# Sheet1.net
KiCad netlist of a schematic drawn in Altium Designer
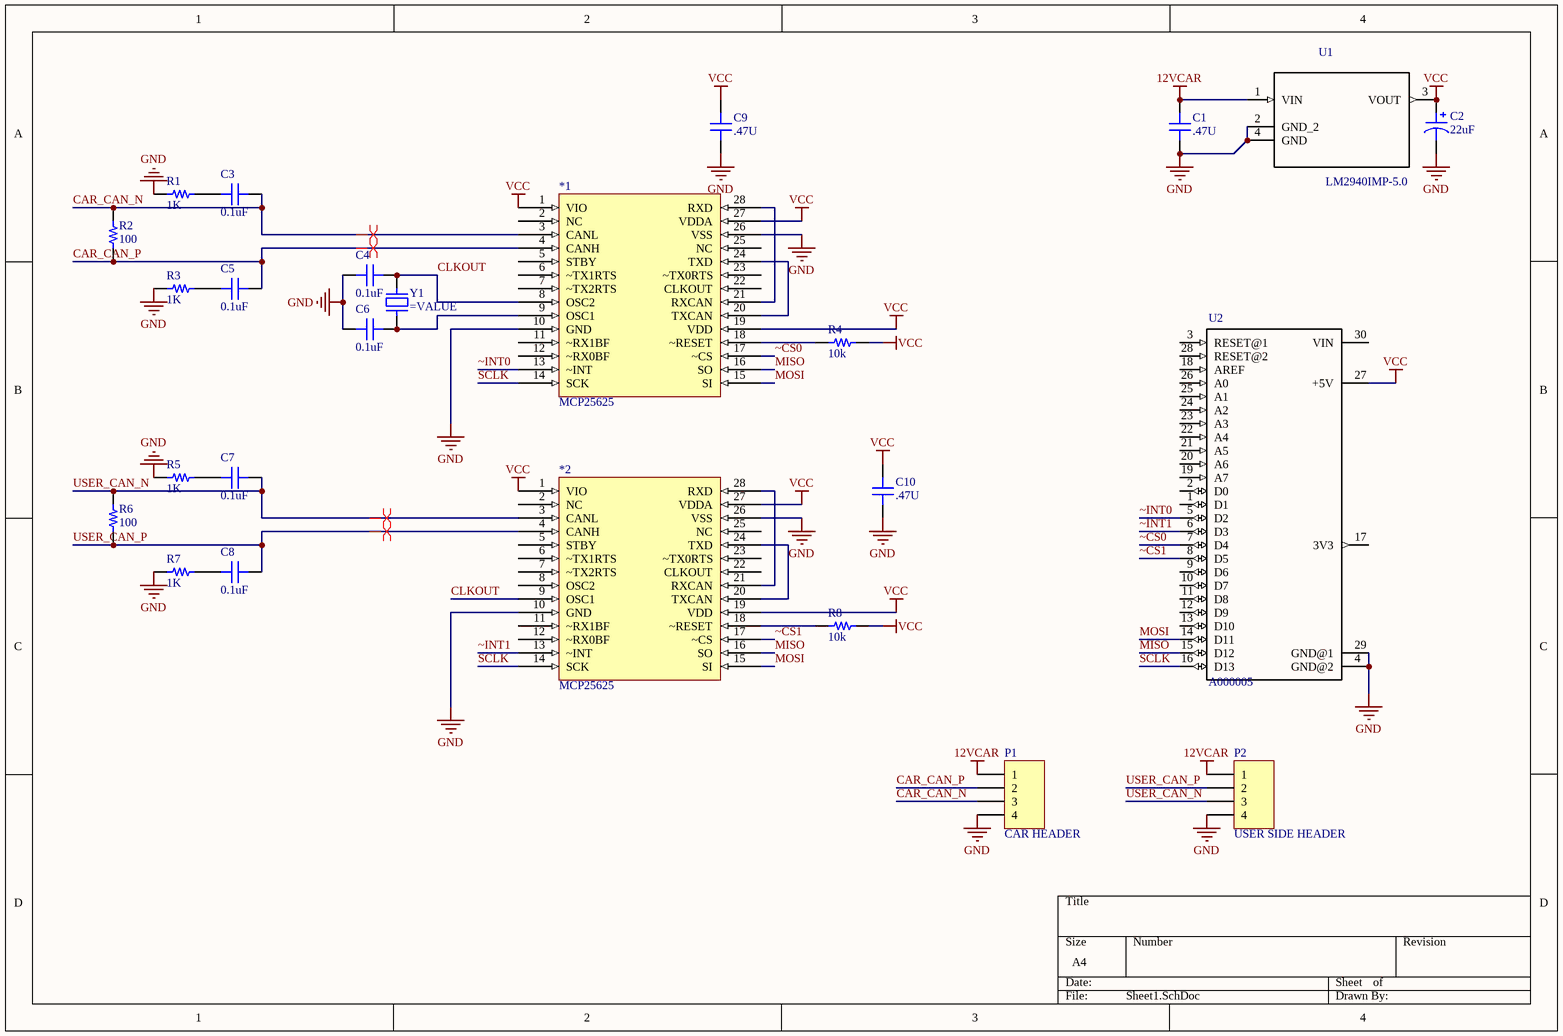
[diagram p0: Sheet1.SchDoc]

(export (version "E")
  (design (tool "Eeschema 10.0.6"))
  (components
    (comp (ref "*1")
      (value "MCP25625")
      (footprint "SOP65P780X200-28L")
      (libsource (lib "Schlib1") (part "MCP25625"))
    )
    (comp (ref "*2")
      (value "MCP25625")
      (footprint "SOP65P780X200-28L")
      (libsource (lib "Schlib1") (part "MCP25625"))
    )
    (comp (ref "C1")
      (value ".47U")
      (footprint "CAP 0805/2012")
      (description "SMT Capacitor")
      (libsource (lib "Passives") (part "Capacitor"))
    )
    (comp (ref "C2")
      (value "22uF")
      (footprint "CAP POL 2917/7343")
      (description "SMT Polarised Capacitor")
      (libsource (lib "Passives") (part "Polarised Capacitor"))
    )
    (comp (ref "C3")
      (value "0.1uF")
      (footprint "CAP 0805/2012")
      (description "SMT Capacitor")
      (libsource (lib "Passives") (part "Capacitor"))
    )
    (comp (ref "C4")
      (value "0.1uF")
      (footprint "CAP 0805/2012")
      (description "SMT Capacitor")
      (libsource (lib "Passives") (part "Capacitor"))
    )
    (comp (ref "C5")
      (value "0.1uF")
      (footprint "CAP 0805/2012")
      (description "SMT Capacitor")
      (libsource (lib "Passives") (part "Capacitor"))
    )
    (comp (ref "C6")
      (value "0.1uF")
      (footprint "CAP 0805/2012")
      (description "SMT Capacitor")
      (libsource (lib "Passives") (part "Capacitor"))
    )
    (comp (ref "C7")
      (value "0.1uF")
      (footprint "CAP 0805/2012")
      (description "SMT Capacitor")
      (libsource (lib "Passives") (part "Capacitor"))
    )
    (comp (ref "C8")
      (value "0.1uF")
      (footprint "CAP 0805/2012")
      (description "SMT Capacitor")
      (libsource (lib "Passives") (part "Capacitor"))
    )
    (comp (ref "C9")
      (value ".47U")
      (footprint "CAP 0805/2012")
      (description "SMT Capacitor")
      (libsource (lib "Passives") (part "Capacitor"))
    )
    (comp (ref "C10")
      (value ".47U")
      (footprint "CAP 0805/2012")
      (description "SMT Capacitor")
      (libsource (lib "Passives") (part "Capacitor"))
    )
    (comp (ref "P1")
      (value "CAR HEADER")
      (footprint "HDR1X4")
      (description "Header, 4-Pin")
      (fields (field (name "PUBLISHER") "Altium Limited"))
      (libsource (lib "Miscellaneous Connectors") (part "Header 4"))
    )
    (comp (ref "P2")
      (value "USER SIDE HEADER")
      (footprint "HDR1X4")
      (description "Header, 4-Pin")
      (fields (field (name "PUBLISHER") "Altium Limited"))
      (libsource (lib "Miscellaneous Connectors") (part "Header 4"))
    )
    (comp (ref "R1")
      (value "1K")
      (footprint "RES 0805/2012")
      (description "SMT Resistor")
      (libsource (lib "Passives") (part "Resistor"))
    )
    (comp (ref "R2")
      (value "100")
      (footprint "RES 0805/2012")
      (description "SMT Resistor")
      (libsource (lib "Passives") (part "Resistor"))
    )
    (comp (ref "R3")
      (value "1K")
      (footprint "RES 0805/2012")
      (description "SMT Resistor")
      (libsource (lib "Passives") (part "Resistor"))
    )
    (comp (ref "R4")
      (value "10k")
      (footprint "RES 0805/2012")
      (description "SMT Resistor")
      (libsource (lib "Passives") (part "Resistor"))
    )
    (comp (ref "R5")
      (value "1K")
      (footprint "RES 0805/2012")
      (description "SMT Resistor")
      (libsource (lib "Passives") (part "Resistor"))
    )
    (comp (ref "R6")
      (value "100")
      (footprint "RES 0805/2012")
      (description "SMT Resistor")
      (libsource (lib "Passives") (part "Resistor"))
    )
    (comp (ref "R7")
      (value "1K")
      (footprint "RES 0805/2012")
      (description "SMT Resistor")
      (libsource (lib "Passives") (part "Resistor"))
    )
    (comp (ref "R8")
      (value "10k")
      (footprint "RES 0805/2012")
      (description "SMT Resistor")
      (libsource (lib "Passives") (part "Resistor"))
    )
    (comp (ref "U1")
      (value "LM2940IMP-5.0")
      (footprint "SOT230P696X180-4N")
      (description "IC REG LINEAR 5V 1A SOT223-4")
      (fields (field (name "MF") "Texas Instruments") (field (name "MP") "LM2940IMP-5.0/NOPB"))
      (libsource (lib "LM2940IMP-5.0") (part "LM2940IMP-5.0"))
    )
    (comp (ref "U2")
      (value "A000005")
      (footprint "ARDUINO_A000005")
      (description "ARDUINO NANO BOARD")
      (fields (field (name "MF") "Arduino") (field (name "DIGI-KEY_PART_NUMBER") "1050-1001-ND"))
      (libsource (lib "A000005") (part "A000005"))
    )
    (comp (ref "Y1")
      (value "~")
      (footprint "XTAL_HC49P488W45L1150T500H350")
      (description "SMT Crystal")
      (libsource (lib "Crystals") (part "Abracon Crystal ABS07"))
    )
  )
  (nets
    (net (code "1") (name "/CAR_CAN_N") (class "Default")
      (node (ref "*1") (pin "3") (pinfunction "CANL_3") (pintype "input"))
      (node (ref "C3") (pin "1") (pinfunction "1_1") (pintype "passive"))
      (node (ref "P1") (pin "3") (pinfunction "3_3") (pintype "passive"))
      (node (ref "R2") (pin "2") (pinfunction "2_2") (pintype "passive"))
    )
    (net (code "2") (name "/CAR_CAN_P") (class "Default")
      (node (ref "*1") (pin "4") (pinfunction "CANH_4") (pintype "input"))
      (node (ref "C5") (pin "1") (pinfunction "1_1") (pintype "passive"))
      (node (ref "P1") (pin "2") (pinfunction "2_2") (pintype "passive"))
      (node (ref "R2") (pin "1") (pinfunction "1_1") (pintype "passive"))
    )
    (net (code "3") (name "/CLKOUT") (class "Default")
      (node (ref "*1") (pin "8") (pinfunction "OSC2_8") (pintype "input"))
      (node (ref "*2") (pin "9") (pinfunction "OSC1_9") (pintype "input"))
      (node (ref "C4") (pin "2") (pinfunction "2_2") (pintype "passive"))
      (node (ref "Y1") (pin "2") (pinfunction "2_2") (pintype "passive"))
    )
    (net (code "4") (name "/MISO") (class "Default")
      (node (ref "*1") (pin "16") (pinfunction "SO_16") (pintype "input"))
      (node (ref "*2") (pin "16") (pinfunction "SO_16") (pintype "input"))
      (node (ref "U2") (pin "15") (pinfunction "D12_15") (pintype "bidirectional"))
    )
    (net (code "5") (name "/MOSI") (class "Default")
      (node (ref "*1") (pin "15") (pinfunction "SI_15") (pintype "input"))
      (node (ref "*2") (pin "15") (pinfunction "SI_15") (pintype "input"))
      (node (ref "U2") (pin "14") (pinfunction "D11_14") (pintype "bidirectional"))
    )
    (net (code "6") (name "/SCLK") (class "Default")
      (node (ref "*1") (pin "14") (pinfunction "SCK_14") (pintype "input"))
      (node (ref "*2") (pin "14") (pinfunction "SCK_14") (pintype "input"))
      (node (ref "U2") (pin "16") (pinfunction "D13_16") (pintype "bidirectional"))
    )
    (net (code "7") (name "/USER_CAN_N") (class "Default")
      (node (ref "*2") (pin "3") (pinfunction "CANL_3") (pintype "input"))
      (node (ref "C7") (pin "1") (pinfunction "1_1") (pintype "passive"))
      (node (ref "P2") (pin "3") (pinfunction "3_3") (pintype "passive"))
      (node (ref "R6") (pin "2") (pinfunction "2_2") (pintype "passive"))
    )
    (net (code "8") (name "/USER_CAN_P") (class "Default")
      (node (ref "*2") (pin "4") (pinfunction "CANH_4") (pintype "input"))
      (node (ref "C8") (pin "1") (pinfunction "1_1") (pintype "passive"))
      (node (ref "P2") (pin "2") (pinfunction "2_2") (pintype "passive"))
      (node (ref "R6") (pin "1") (pinfunction "1_1") (pintype "passive"))
    )
    (net (code "9") (name "/~CS0") (class "Default")
      (node (ref "*1") (pin "17") (pinfunction "~CS_17") (pintype "input"))
      (node (ref "U2") (pin "7") (pinfunction "D4_7") (pintype "bidirectional"))
    )
    (net (code "10") (name "/~CS1") (class "Default")
      (node (ref "*2") (pin "17") (pinfunction "~CS_17") (pintype "input"))
      (node (ref "U2") (pin "8") (pinfunction "D5_8") (pintype "bidirectional"))
    )
    (net (code "11") (name "/~INT0") (class "Default")
      (node (ref "*1") (pin "13") (pinfunction "~INT_13") (pintype "input"))
      (node (ref "U2") (pin "5") (pinfunction "D2_5") (pintype "bidirectional"))
    )
    (net (code "12") (name "/~INT1") (class "Default")
      (node (ref "*2") (pin "13") (pinfunction "~INT_13") (pintype "input"))
      (node (ref "U2") (pin "6") (pinfunction "D3_6") (pintype "bidirectional"))
    )
    (net (code "13") (name "12VCAR") (class "Default")
      (node (ref "C1") (pin "2") (pinfunction "2_2") (pintype "passive"))
      (node (ref "P1") (pin "1") (pinfunction "1_1") (pintype "passive"))
      (node (ref "P2") (pin "1") (pinfunction "1_1") (pintype "passive"))
      (node (ref "U1") (pin "1") (pinfunction "VIN_1") (pintype "input"))
    )
    (net (code "14") (name "GND") (class "Default")
      (node (ref "*1") (pin "10") (pinfunction "GND_10") (pintype "input"))
      (node (ref "*1") (pin "26") (pinfunction "VSS_26") (pintype "input"))
      (node (ref "*2") (pin "10") (pinfunction "GND_10") (pintype "input"))
      (node (ref "*2") (pin "26") (pinfunction "VSS_26") (pintype "input"))
      (node (ref "C1") (pin "1") (pinfunction "1_1") (pintype "passive"))
      (node (ref "C10") (pin "1") (pinfunction "1_1") (pintype "passive"))
      (node (ref "C2") (pin "2") (pinfunction "2_2") (pintype "passive"))
      (node (ref "C4") (pin "1") (pinfunction "1_1") (pintype "passive"))
      (node (ref "C6") (pin "1") (pinfunction "1_1") (pintype "passive"))
      (node (ref "C9") (pin "1") (pinfunction "1_1") (pintype "passive"))
      (node (ref "P1") (pin "4") (pinfunction "4_4") (pintype "passive"))
      (node (ref "P2") (pin "4") (pinfunction "4_4") (pintype "passive"))
      (node (ref "R1") (pin "1") (pinfunction "1_1") (pintype "passive"))
      (node (ref "R3") (pin "1") (pinfunction "1_1") (pintype "passive"))
      (node (ref "R5") (pin "1") (pinfunction "1_1") (pintype "passive"))
      (node (ref "R7") (pin "1") (pinfunction "1_1") (pintype "passive"))
      (node (ref "U1") (pin "2") (pinfunction "GND_2_2") (pintype "passive"))
      (node (ref "U1") (pin "4") (pinfunction "GND_4") (pintype "passive"))
      (node (ref "U2") (pin "29") (pinfunction "GND@1_29") (pintype "power_in"))
      (node (ref "U2") (pin "4") (pinfunction "GND@2_4") (pintype "power_in"))
    )
    (net (code "15") (name "Net-(*1-OSC1)") (class "Default")
      (node (ref "*1") (pin "9") (pinfunction "OSC1_9") (pintype "input"))
      (node (ref "C6") (pin "2") (pinfunction "2_2") (pintype "passive"))
      (node (ref "Y1") (pin "1") (pinfunction "1_1") (pintype "passive"))
    )
    (net (code "16") (name "Net-(*1-RXCAN)") (class "Default")
      (node (ref "*1") (pin "21") (pinfunction "RXCAN_21") (pintype "input"))
      (node (ref "*1") (pin "28") (pinfunction "RXD_28") (pintype "input"))
    )
    (net (code "17") (name "Net-(*1-TXCAN)") (class "Default")
      (node (ref "*1") (pin "20") (pinfunction "TXCAN_20") (pintype "input"))
      (node (ref "*1") (pin "24") (pinfunction "TXD_24") (pintype "input"))
    )
    (net (code "18") (name "Net-(*1-~RESET)") (class "Default")
      (node (ref "*1") (pin "18") (pinfunction "~RESET_18") (pintype "input"))
      (node (ref "R4") (pin "1") (pinfunction "1_1") (pintype "passive"))
    )
    (net (code "19") (name "Net-(*2-RXCAN)") (class "Default")
      (node (ref "*2") (pin "21") (pinfunction "RXCAN_21") (pintype "input"))
      (node (ref "*2") (pin "28") (pinfunction "RXD_28") (pintype "input"))
    )
    (net (code "20") (name "Net-(*2-TXCAN)") (class "Default")
      (node (ref "*2") (pin "20") (pinfunction "TXCAN_20") (pintype "input"))
      (node (ref "*2") (pin "24") (pinfunction "TXD_24") (pintype "input"))
    )
    (net (code "21") (name "Net-(*2-~RESET)") (class "Default")
      (node (ref "*2") (pin "18") (pinfunction "~RESET_18") (pintype "input"))
      (node (ref "R8") (pin "1") (pinfunction "1_1") (pintype "passive"))
    )
    (net (code "22") (name "Net-(C3-Pad2)") (class "Default")
      (node (ref "C3") (pin "2") (pinfunction "2_2") (pintype "passive"))
      (node (ref "R1") (pin "2") (pinfunction "2_2") (pintype "passive"))
    )
    (net (code "23") (name "Net-(C5-Pad2)") (class "Default")
      (node (ref "C5") (pin "2") (pinfunction "2_2") (pintype "passive"))
      (node (ref "R3") (pin "2") (pinfunction "2_2") (pintype "passive"))
    )
    (net (code "24") (name "Net-(C7-Pad2)") (class "Default")
      (node (ref "C7") (pin "2") (pinfunction "2_2") (pintype "passive"))
      (node (ref "R5") (pin "2") (pinfunction "2_2") (pintype "passive"))
    )
    (net (code "25") (name "Net-(C8-Pad2)") (class "Default")
      (node (ref "C8") (pin "2") (pinfunction "2_2") (pintype "passive"))
      (node (ref "R7") (pin "2") (pinfunction "2_2") (pintype "passive"))
    )
    (net (code "26") (name "VCC") (class "Default")
      (node (ref "*1") (pin "1") (pinfunction "VIO_1") (pintype "input"))
      (node (ref "*1") (pin "19") (pinfunction "VDD_19") (pintype "input"))
      (node (ref "*1") (pin "27") (pinfunction "VDDA_27") (pintype "input"))
      (node (ref "*2") (pin "1") (pinfunction "VIO_1") (pintype "input"))
      (node (ref "*2") (pin "19") (pinfunction "VDD_19") (pintype "input"))
      (node (ref "*2") (pin "27") (pinfunction "VDDA_27") (pintype "input"))
      (node (ref "C10") (pin "2") (pinfunction "2_2") (pintype "passive"))
      (node (ref "C2") (pin "1") (pinfunction "1_1") (pintype "passive"))
      (node (ref "C9") (pin "2") (pinfunction "2_2") (pintype "passive"))
      (node (ref "R4") (pin "2") (pinfunction "2_2") (pintype "passive"))
      (node (ref "R8") (pin "2") (pinfunction "2_2") (pintype "passive"))
      (node (ref "U1") (pin "3") (pinfunction "VOUT_3") (pintype "output"))
      (node (ref "U2") (pin "27") (pinfunction "+5V_27") (pintype "power_in"))
    )
    (net (code "27") (name "unconnected-(*1-CLKOUT-Pad22)") (class "Default")
      (node (ref "*1") (pin "22") (pinfunction "CLKOUT_22") (pintype "input"))
    )
    (net (code "28") (name "unconnected-(*1-NC-Pad2)") (class "Default")
      (node (ref "*1") (pin "2") (pinfunction "NC_2") (pintype "input"))
    )
    (net (code "29") (name "unconnected-(*1-NC-Pad25)") (class "Default")
      (node (ref "*1") (pin "25") (pinfunction "NC_25") (pintype "input"))
    )
    (net (code "30") (name "unconnected-(*1-STBY-Pad5)") (class "Default")
      (node (ref "*1") (pin "5") (pinfunction "STBY_5") (pintype "input"))
    )
    (net (code "31") (name "unconnected-(*1-~RX0BF-Pad12)") (class "Default")
      (node (ref "*1") (pin "12") (pinfunction "~RX0BF_12") (pintype "input"))
    )
    (net (code "32") (name "unconnected-(*1-~RX1BF-Pad11)") (class "Default")
      (node (ref "*1") (pin "11") (pinfunction "~RX1BF_11") (pintype "input"))
    )
    (net (code "33") (name "unconnected-(*1-~TX0RTS-Pad23)") (class "Default")
      (node (ref "*1") (pin "23") (pinfunction "~TX0RTS_23") (pintype "input"))
    )
    (net (code "34") (name "unconnected-(*1-~TX1RTS-Pad6)") (class "Default")
      (node (ref "*1") (pin "6") (pinfunction "~TX1RTS_6") (pintype "input"))
    )
    (net (code "35") (name "unconnected-(*1-~TX2RTS-Pad7)") (class "Default")
      (node (ref "*1") (pin "7") (pinfunction "~TX2RTS_7") (pintype "input"))
    )
    (net (code "36") (name "unconnected-(*2-CLKOUT-Pad22)") (class "Default")
      (node (ref "*2") (pin "22") (pinfunction "CLKOUT_22") (pintype "input"))
    )
    (net (code "37") (name "unconnected-(*2-NC-Pad2)") (class "Default")
      (node (ref "*2") (pin "2") (pinfunction "NC_2") (pintype "input"))
    )
    (net (code "38") (name "unconnected-(*2-NC-Pad25)") (class "Default")
      (node (ref "*2") (pin "25") (pinfunction "NC_25") (pintype "input"))
    )
    (net (code "39") (name "unconnected-(*2-OSC2-Pad8)") (class "Default")
      (node (ref "*2") (pin "8") (pinfunction "OSC2_8") (pintype "input"))
    )
    (net (code "40") (name "unconnected-(*2-STBY-Pad5)") (class "Default")
      (node (ref "*2") (pin "5") (pinfunction "STBY_5") (pintype "input"))
    )
    (net (code "41") (name "unconnected-(*2-~RX0BF-Pad12)") (class "Default")
      (node (ref "*2") (pin "12") (pinfunction "~RX0BF_12") (pintype "input"))
    )
    (net (code "42") (name "unconnected-(*2-~RX1BF-Pad11)") (class "Default")
      (node (ref "*2") (pin "11") (pinfunction "~RX1BF_11") (pintype "input"))
    )
    (net (code "43") (name "unconnected-(*2-~TX0RTS-Pad23)") (class "Default")
      (node (ref "*2") (pin "23") (pinfunction "~TX0RTS_23") (pintype "input"))
    )
    (net (code "44") (name "unconnected-(*2-~TX1RTS-Pad6)") (class "Default")
      (node (ref "*2") (pin "6") (pinfunction "~TX1RTS_6") (pintype "input"))
    )
    (net (code "45") (name "unconnected-(*2-~TX2RTS-Pad7)") (class "Default")
      (node (ref "*2") (pin "7") (pinfunction "~TX2RTS_7") (pintype "input"))
    )
    (net (code "46") (name "unconnected-(U2-3V3-Pad17)") (class "Default")
      (node (ref "U2") (pin "17") (pinfunction "3V3_17") (pintype "output"))
    )
    (net (code "47") (name "unconnected-(U2-A0-Pad26)") (class "Default")
      (node (ref "U2") (pin "26") (pinfunction "A0_26") (pintype "input"))
    )
    (net (code "48") (name "unconnected-(U2-A1-Pad25)") (class "Default")
      (node (ref "U2") (pin "25") (pinfunction "A1_25") (pintype "input"))
    )
    (net (code "49") (name "unconnected-(U2-A2-Pad24)") (class "Default")
      (node (ref "U2") (pin "24") (pinfunction "A2_24") (pintype "input"))
    )
    (net (code "50") (name "unconnected-(U2-A3-Pad23)") (class "Default")
      (node (ref "U2") (pin "23") (pinfunction "A3_23") (pintype "input"))
    )
    (net (code "51") (name "unconnected-(U2-A4-Pad22)") (class "Default")
      (node (ref "U2") (pin "22") (pinfunction "A4_22") (pintype "input"))
    )
    (net (code "52") (name "unconnected-(U2-A5-Pad21)") (class "Default")
      (node (ref "U2") (pin "21") (pinfunction "A5_21") (pintype "input"))
    )
    (net (code "53") (name "unconnected-(U2-A6-Pad20)") (class "Default")
      (node (ref "U2") (pin "20") (pinfunction "A6_20") (pintype "input"))
    )
    (net (code "54") (name "unconnected-(U2-A7-Pad19)") (class "Default")
      (node (ref "U2") (pin "19") (pinfunction "A7_19") (pintype "input"))
    )
    (net (code "55") (name "unconnected-(U2-AREF-Pad18)") (class "Default")
      (node (ref "U2") (pin "18") (pinfunction "AREF_18") (pintype "input"))
    )
    (net (code "56") (name "unconnected-(U2-D0-Pad2)") (class "Default")
      (node (ref "U2") (pin "2") (pinfunction "D0_2") (pintype "bidirectional"))
    )
    (net (code "57") (name "unconnected-(U2-D1-Pad1)") (class "Default")
      (node (ref "U2") (pin "1") (pinfunction "D1_1") (pintype "bidirectional"))
    )
    (net (code "58") (name "unconnected-(U2-D6-Pad9)") (class "Default")
      (node (ref "U2") (pin "9") (pinfunction "D6_9") (pintype "bidirectional"))
    )
    (net (code "59") (name "unconnected-(U2-D7-Pad10)") (class "Default")
      (node (ref "U2") (pin "10") (pinfunction "D7_10") (pintype "bidirectional"))
    )
    (net (code "60") (name "unconnected-(U2-D8-Pad11)") (class "Default")
      (node (ref "U2") (pin "11") (pinfunction "D8_11") (pintype "bidirectional"))
    )
    (net (code "61") (name "unconnected-(U2-D9-Pad12)") (class "Default")
      (node (ref "U2") (pin "12") (pinfunction "D9_12") (pintype "bidirectional"))
    )
    (net (code "62") (name "unconnected-(U2-D10-Pad13)") (class "Default")
      (node (ref "U2") (pin "13") (pinfunction "D10_13") (pintype "bidirectional"))
    )
    (net (code "63") (name "unconnected-(U2-RESET@1-Pad3)") (class "Default")
      (node (ref "U2") (pin "3") (pinfunction "RESET@1_3") (pintype "input"))
    )
    (net (code "64") (name "unconnected-(U2-RESET@2-Pad28)") (class "Default")
      (node (ref "U2") (pin "28") (pinfunction "RESET@2_28") (pintype "input"))
    )
    (net (code "65") (name "unconnected-(U2-VIN-Pad30)") (class "Default")
      (node (ref "U2") (pin "30") (pinfunction "VIN_30") (pintype "power_in"))
    )
  )
)
